# flowerfriend_rev3.net
KiCad netlist of a schematic drawn in EAGLE
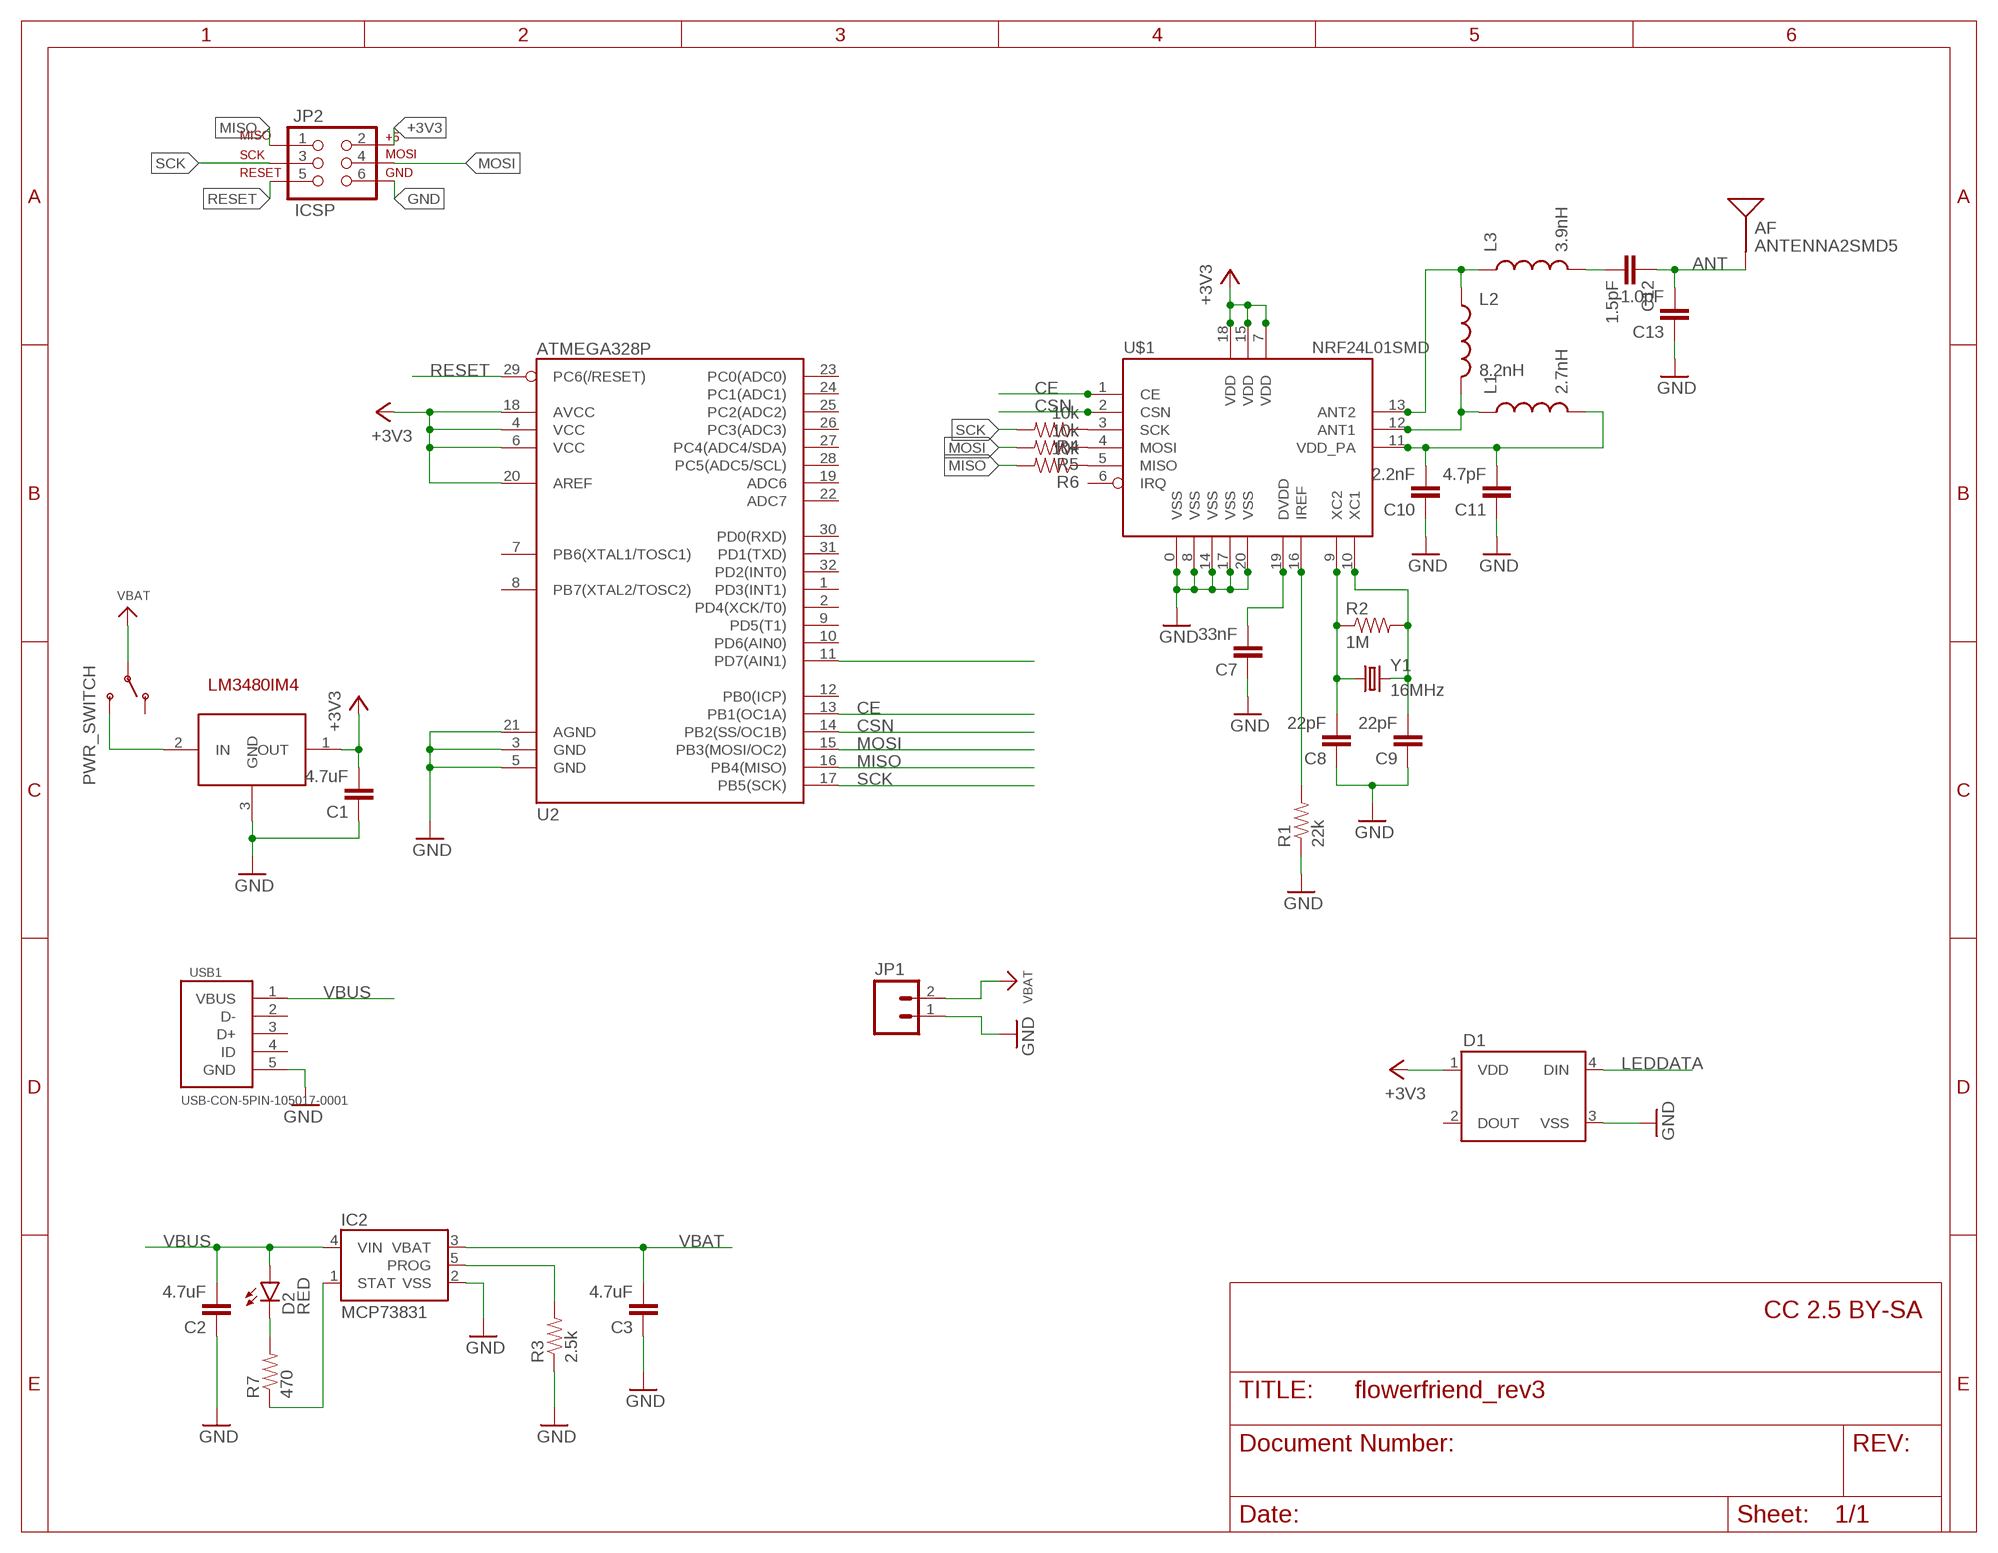
[diagram p0: schematic, sheet 1]

(export (version "E")
  (design (tool "Eeschema 10.0.6"))
  (components
    (comp (ref "AF")
      (value "ANTENNA2SMD5")
      (footprint "eagle-import:ANTENNA-CHIP5")
      (libsource (lib "eagle-import") (part "ANTENNA2SMD5"))
    )
    (comp (ref "C1")
      (value "4.7uF")
      (footprint "eagle-import:0805")
      (libsource (lib "eagle-import") (part "CAP0805"))
    )
    (comp (ref "C2")
      (value "4.7uF")
      (footprint "eagle-import:0805")
      (libsource (lib "eagle-import") (part "CAP0805"))
    )
    (comp (ref "C3")
      (value "4.7uF")
      (footprint "eagle-import:0805")
      (libsource (lib "eagle-import") (part "CAP0805"))
    )
    (comp (ref "C7")
      (value "33nF")
      (footprint "eagle-import:0805")
      (libsource (lib "eagle-import") (part "CAP0805"))
    )
    (comp (ref "C8")
      (value "22pF")
      (footprint "eagle-import:0805")
      (libsource (lib "eagle-import") (part "CAP0805"))
    )
    (comp (ref "C9")
      (value "22pF")
      (footprint "eagle-import:0805")
      (libsource (lib "eagle-import") (part "CAP0805"))
    )
    (comp (ref "C10")
      (value "2.2nF")
      (footprint "eagle-import:0805")
      (libsource (lib "eagle-import") (part "CAP0805"))
    )
    (comp (ref "C11")
      (value "4.7pF")
      (footprint "eagle-import:0805")
      (libsource (lib "eagle-import") (part "CAP0805"))
    )
    (comp (ref "C12")
      (value "1.5pF")
      (footprint "eagle-import:0805")
      (libsource (lib "eagle-import") (part "CAP0805"))
    )
    (comp (ref "C13")
      (value "1.0pF")
      (footprint "eagle-import:0805")
      (libsource (lib "eagle-import") (part "CAP0805"))
    )
    (comp (ref "D1")
      (value "WS2812B")
      (footprint "eagle-import:WS2812B")
      (libsource (lib "eagle-import") (part "WS2812B"))
    )
    (comp (ref "D2")
      (value "RED")
      (footprint "eagle-import:LED-0603")
      (libsource (lib "eagle-import") (part "LED-RED0603"))
    )
    (comp (ref "IC1")
      (value "LM3480IM4")
      (footprint "eagle-import:SOT23-3")
      (libsource (lib "eagle-import") (part "LM3480IM4"))
    )
    (comp (ref "IC2")
      (value "MCP73831")
      (footprint "eagle-import:SOT23-5")
      (libsource (lib "eagle-import") (part "MCP73831"))
    )
    (comp (ref "JP1")
      (value "M02PTH")
      (footprint "eagle-import:1X02")
      (libsource (lib "eagle-import") (part "M02PTH"))
    )
    (comp (ref "JP2")
      (value "ICSP")
      (footprint "eagle-import:2X3")
      (libsource (lib "eagle-import") (part "AVR_SPI_PRG_6PTH"))
    )
    (comp (ref "L1")
      (value "2.7nH")
      (footprint "eagle-import:0805")
      (libsource (lib "eagle-import") (part "INDUCTOR0805"))
    )
    (comp (ref "L2")
      (value "8.2nH")
      (footprint "eagle-import:0805")
      (libsource (lib "eagle-import") (part "INDUCTOR0805"))
    )
    (comp (ref "L3")
      (value "3.9nH")
      (footprint "eagle-import:0805")
      (libsource (lib "eagle-import") (part "INDUCTOR0805"))
    )
    (comp (ref "PWR_SWITCH")
      (value "SWITCH_SPDT")
      (footprint "eagle-import:KPS-1290")
      (libsource (lib "eagle-import") (part "SWITCH_SPDT"))
    )
    (comp (ref "R1")
      (value "22k")
      (footprint "eagle-import:0805")
      (libsource (lib "eagle-import") (part "RESISTOR0805-RES"))
    )
    (comp (ref "R2")
      (value "1M")
      (footprint "eagle-import:0805")
      (libsource (lib "eagle-import") (part "RESISTOR0805-RES"))
    )
    (comp (ref "R3")
      (value "2.5k")
      (footprint "eagle-import:0805")
      (libsource (lib "eagle-import") (part "RESISTOR0805-RES"))
    )
    (comp (ref "R4")
      (value "10k")
      (footprint "eagle-import:0805")
      (libsource (lib "eagle-import") (part "RESISTOR0805-RES"))
    )
    (comp (ref "R5")
      (value "10k")
      (footprint "eagle-import:0805")
      (libsource (lib "eagle-import") (part "RESISTOR0805-RES"))
    )
    (comp (ref "R6")
      (value "10k")
      (footprint "eagle-import:0805")
      (libsource (lib "eagle-import") (part "RESISTOR0805-RES"))
    )
    (comp (ref "R7")
      (value "470")
      (footprint "eagle-import:0805")
      (libsource (lib "eagle-import") (part "RESISTOR0805-RES"))
    )
    (comp (ref "U$1")
      (value "NRF24L01SMD")
      (footprint "eagle-import:QFN20")
      (libsource (lib "eagle-import") (part "NRF24L01SMD"))
    )
    (comp (ref "U2")
      (value "ATMEGA328P")
      (footprint "eagle-import:TQFP32-08")
      (libsource (lib "eagle-import") (part "ATMEGA328_SMT"))
    )
    (comp (ref "USB1")
      (value "USB-CON-5PIN-105017-0001")
      (footprint "eagle-import:USB-MICRO-MOLEX-105017-0001")
      (libsource (lib "eagle-import") (part "USB-CON-5PIN-105017-0001"))
    )
    (comp (ref "Y1")
      (value "16MHz")
      (footprint "eagle-import:CRYSTAL-SMD-5X3")
      (libsource (lib "eagle-import") (part "CRYSTAL5X3"))
    )
  )
  (nets
    (net (code "1") (name "+3V3") (class "Default")
      (node (ref "C1") (pin "2") (pinfunction "2_2") (pintype "passive"))
      (node (ref "D1") (pin "1") (pinfunction "VDD_1") (pintype "power_in"))
      (node (ref "IC1") (pin "1") (pinfunction "OUT_1") (pintype "bidirectional"))
      (node (ref "JP2") (pin "2") (pinfunction "2_2") (pintype "passive"))
      (node (ref "U$1") (pin "15") (pinfunction "VDD_15") (pintype "power_in"))
      (node (ref "U$1") (pin "18") (pinfunction "VDD_18") (pintype "power_in"))
      (node (ref "U$1") (pin "7") (pinfunction "VDD_7") (pintype "power_in"))
      (node (ref "U2") (pin "18") (pinfunction "AVCC_18") (pintype "bidirectional"))
      (node (ref "U2") (pin "20") (pinfunction "AREF_20") (pintype "bidirectional"))
      (node (ref "U2") (pin "4") (pinfunction "VCC_4") (pintype "bidirectional"))
      (node (ref "U2") (pin "6") (pinfunction "VCC_6") (pintype "bidirectional"))
    )
    (net (code "2") (name "/ANT") (class "Default")
      (node (ref "AF") (pin "FEED") (pinfunction "SIGNAL_FEED") (pintype "bidirectional"))
      (node (ref "C12") (pin "1") (pinfunction "1_1") (pintype "passive"))
      (node (ref "C13") (pin "2") (pinfunction "2_2") (pintype "passive"))
    )
    (net (code "3") (name "/CE") (class "Default")
      (node (ref "U$1") (pin "1") (pinfunction "CE_1") (pintype "input"))
      (node (ref "U2") (pin "13") (pinfunction "PB1(OC1A)_13") (pintype "bidirectional"))
    )
    (net (code "4") (name "/CSN") (class "Default")
      (node (ref "U$1") (pin "2") (pinfunction "CSN_2") (pintype "input"))
      (node (ref "U2") (pin "14") (pinfunction "PB2(SS/OC1B)_14") (pintype "bidirectional"))
    )
    (net (code "5") (name "/LEDDATA") (class "Default")
      (node (ref "D1") (pin "4") (pinfunction "DIN_4") (pintype "input"))
      (node (ref "U2") (pin "11") (pinfunction "PD7(AIN1)_11") (pintype "bidirectional"))
    )
    (net (code "6") (name "/VBUS") (class "Default")
      (node (ref "C2") (pin "2") (pinfunction "2_2") (pintype "passive"))
      (node (ref "D2") (pin "A") (pinfunction "A_A") (pintype "passive"))
      (node (ref "IC2") (pin "4") (pinfunction "VIN_4") (pintype "power_in"))
      (node (ref "USB1") (pin "1") (pinfunction "VBUS_1") (pintype "power_in"))
    )
    (net (code "7") (name "GND") (class "Default")
      (node (ref "C1") (pin "1") (pinfunction "1_1") (pintype "passive"))
      (node (ref "C10") (pin "1") (pinfunction "1_1") (pintype "passive"))
      (node (ref "C11") (pin "1") (pinfunction "1_1") (pintype "passive"))
      (node (ref "C13") (pin "1") (pinfunction "1_1") (pintype "passive"))
      (node (ref "C2") (pin "1") (pinfunction "1_1") (pintype "passive"))
      (node (ref "C3") (pin "1") (pinfunction "1_1") (pintype "passive"))
      (node (ref "C7") (pin "1") (pinfunction "1_1") (pintype "passive"))
      (node (ref "C8") (pin "1") (pinfunction "1_1") (pintype "passive"))
      (node (ref "C9") (pin "1") (pinfunction "1_1") (pintype "passive"))
      (node (ref "D1") (pin "3") (pinfunction "VSS_3") (pintype "power_in"))
      (node (ref "IC1") (pin "3") (pinfunction "GND_3") (pintype "bidirectional"))
      (node (ref "IC2") (pin "2") (pinfunction "VSS_2") (pintype "power_in"))
      (node (ref "JP1") (pin "1") (pinfunction "1_1") (pintype "passive"))
      (node (ref "JP2") (pin "6") (pinfunction "6_6") (pintype "passive"))
      (node (ref "R1") (pin "1") (pinfunction "1_1") (pintype "passive"))
      (node (ref "R3") (pin "1") (pinfunction "1_1") (pintype "passive"))
      (node (ref "U$1") (pin "0") (pinfunction "VSS_0") (pintype "power_in"))
      (node (ref "U$1") (pin "14") (pinfunction "VSS_14") (pintype "power_in"))
      (node (ref "U$1") (pin "17") (pinfunction "VSS_17") (pintype "power_in"))
      (node (ref "U$1") (pin "20") (pinfunction "VSS_20") (pintype "power_in"))
      (node (ref "U$1") (pin "8") (pinfunction "VSS_8") (pintype "power_in"))
      (node (ref "U2") (pin "21") (pinfunction "AGND_21") (pintype "bidirectional"))
      (node (ref "U2") (pin "3") (pinfunction "GND_3") (pintype "bidirectional"))
      (node (ref "U2") (pin "5") (pinfunction "GND_5") (pintype "bidirectional"))
      (node (ref "USB1") (pin "5") (pinfunction "GND_5") (pintype "power_in"))
    )
    (net (code "8") (name "MISO") (class "Default")
      (node (ref "JP2") (pin "1") (pinfunction "1_1") (pintype "passive"))
      (node (ref "R6") (pin "2") (pinfunction "2_2") (pintype "passive"))
      (node (ref "U2") (pin "16") (pinfunction "PB4(MISO)_16") (pintype "bidirectional"))
    )
    (net (code "9") (name "MOSI") (class "Default")
      (node (ref "JP2") (pin "4") (pinfunction "4_4") (pintype "passive"))
      (node (ref "R5") (pin "2") (pinfunction "2_2") (pintype "passive"))
      (node (ref "U2") (pin "15") (pinfunction "PB3(MOSI/OC2)_15") (pintype "bidirectional"))
    )
    (net (code "10") (name "Net-(C12-Pad2)") (class "Default")
      (node (ref "C12") (pin "2") (pinfunction "2_2") (pintype "passive"))
      (node (ref "L3") (pin "2") (pinfunction "2_2") (pintype "passive"))
    )
    (net (code "11") (name "Net-(D2-PadC)") (class "Default")
      (node (ref "D2") (pin "C") (pinfunction "C_C") (pintype "passive"))
      (node (ref "R7") (pin "2") (pinfunction "2_2") (pintype "passive"))
    )
    (net (code "12") (name "Net-(IC1-IN)") (class "Default")
      (node (ref "IC1") (pin "2") (pinfunction "IN_2") (pintype "bidirectional"))
      (node (ref "PWR_SWITCH") (pin "S") (pinfunction "S_S") (pintype "passive"))
    )
    (net (code "13") (name "Net-(IC2-PROG)") (class "Default")
      (node (ref "IC2") (pin "5") (pinfunction "PROG_5") (pintype "input"))
      (node (ref "R3") (pin "2") (pinfunction "2_2") (pintype "passive"))
    )
    (net (code "14") (name "Net-(IC2-STAT)") (class "Default")
      (node (ref "IC2") (pin "1") (pinfunction "STAT_1") (pintype "output"))
      (node (ref "R7") (pin "1") (pinfunction "1_1") (pintype "passive"))
    )
    (net (code "15") (name "Net-(U$1-ANT1)") (class "Default")
      (node (ref "L1") (pin "1") (pinfunction "1_1") (pintype "passive"))
      (node (ref "L2") (pin "2") (pinfunction "2_2") (pintype "passive"))
      (node (ref "U$1") (pin "12") (pinfunction "ANT1_12") (pintype "output"))
    )
    (net (code "16") (name "Net-(U$1-ANT2)") (class "Default")
      (node (ref "L2") (pin "1") (pinfunction "1_1") (pintype "passive"))
      (node (ref "L3") (pin "1") (pinfunction "1_1") (pintype "passive"))
      (node (ref "U$1") (pin "13") (pinfunction "ANT2_13") (pintype "output"))
    )
    (net (code "17") (name "Net-(U$1-DVDD)") (class "Default")
      (node (ref "C7") (pin "2") (pinfunction "2_2") (pintype "passive"))
      (node (ref "U$1") (pin "19") (pinfunction "DVDD_19") (pintype "power_in"))
    )
    (net (code "18") (name "Net-(U$1-IREF)") (class "Default")
      (node (ref "R1") (pin "2") (pinfunction "2_2") (pintype "passive"))
      (node (ref "U$1") (pin "16") (pinfunction "IREF_16") (pintype "input"))
    )
    (net (code "19") (name "Net-(U$1-MISO)") (class "Default")
      (node (ref "R6") (pin "1") (pinfunction "1_1") (pintype "passive"))
      (node (ref "U$1") (pin "5") (pinfunction "MISO_5") (pintype "output"))
    )
    (net (code "20") (name "Net-(U$1-MOSI)") (class "Default")
      (node (ref "R5") (pin "1") (pinfunction "1_1") (pintype "passive"))
      (node (ref "U$1") (pin "4") (pinfunction "MOSI_4") (pintype "input"))
    )
    (net (code "21") (name "Net-(U$1-SCK)") (class "Default")
      (node (ref "R4") (pin "1") (pinfunction "1_1") (pintype "passive"))
      (node (ref "U$1") (pin "3") (pinfunction "SCK_3") (pintype "input"))
    )
    (net (code "22") (name "Net-(U$1-VDD_PA)") (class "Default")
      (node (ref "C10") (pin "2") (pinfunction "2_2") (pintype "passive"))
      (node (ref "C11") (pin "2") (pinfunction "2_2") (pintype "passive"))
      (node (ref "L1") (pin "2") (pinfunction "2_2") (pintype "passive"))
      (node (ref "U$1") (pin "11") (pinfunction "VDD_PA_11") (pintype "power_in"))
    )
    (net (code "23") (name "Net-(U$1-XC1)") (class "Default")
      (node (ref "C9") (pin "2") (pinfunction "2_2") (pintype "passive"))
      (node (ref "R2") (pin "2") (pinfunction "2_2") (pintype "passive"))
      (node (ref "U$1") (pin "10") (pinfunction "XC1_10") (pintype "input"))
      (node (ref "Y1") (pin "3") (pinfunction "2_3") (pintype "passive"))
    )
    (net (code "24") (name "Net-(U$1-XC2)") (class "Default")
      (node (ref "C8") (pin "2") (pinfunction "2_2") (pintype "passive"))
      (node (ref "R2") (pin "1") (pinfunction "1_1") (pintype "passive"))
      (node (ref "U$1") (pin "9") (pinfunction "XC2_9") (pintype "input"))
      (node (ref "Y1") (pin "1") (pinfunction "1_1") (pintype "passive"))
    )
    (net (code "25") (name "RESET") (class "Default")
      (node (ref "JP2") (pin "5") (pinfunction "5_5") (pintype "passive"))
      (node (ref "U2") (pin "29") (pinfunction "PC6(/RESET)_29") (pintype "bidirectional"))
    )
    (net (code "26") (name "SCK") (class "Default")
      (node (ref "JP2") (pin "3") (pinfunction "3_3") (pintype "passive"))
      (node (ref "R4") (pin "2") (pinfunction "2_2") (pintype "passive"))
      (node (ref "U2") (pin "17") (pinfunction "PB5(SCK)_17") (pintype "bidirectional"))
    )
    (net (code "27") (name "VBAT") (class "Default")
      (node (ref "C3") (pin "2") (pinfunction "2_2") (pintype "passive"))
      (node (ref "IC2") (pin "3") (pinfunction "VBAT_3") (pintype "power_in"))
      (node (ref "JP1") (pin "2") (pinfunction "2_2") (pintype "passive"))
      (node (ref "PWR_SWITCH") (pin "P") (pinfunction "P_P") (pintype "passive"))
    )
    (net (code "28") (name "unconnected-(D1-DOUT-Pad2)") (class "Default")
      (node (ref "D1") (pin "2") (pinfunction "DOUT_2") (pintype "output"))
    )
    (net (code "29") (name "unconnected-(PWR_SWITCH-PadO)") (class "Default")
      (node (ref "PWR_SWITCH") (pin "O") (pinfunction "O_O") (pintype "passive"))
    )
    (net (code "30") (name "unconnected-(U$1-IRQ-Pad6)") (class "Default")
      (node (ref "U$1") (pin "6") (pinfunction "IRQ_6") (pintype "output"))
    )
    (net (code "31") (name "unconnected-(U2-ADC6-Pad19)") (class "Default")
      (node (ref "U2") (pin "19") (pinfunction "ADC6_19") (pintype "bidirectional"))
    )
    (net (code "32") (name "unconnected-(U2-ADC7-Pad22)") (class "Default")
      (node (ref "U2") (pin "22") (pinfunction "ADC7_22") (pintype "bidirectional"))
    )
    (net (code "33") (name "unconnected-(U2-PB0(ICP)-Pad12)") (class "Default")
      (node (ref "U2") (pin "12") (pinfunction "PB0(ICP)_12") (pintype "bidirectional"))
    )
    (net (code "34") (name "unconnected-(U2-PB6(XTAL1{slash}TOSC1)-Pad7)") (class "Default")
      (node (ref "U2") (pin "7") (pinfunction "PB6(XTAL1/TOSC1)_7") (pintype "bidirectional"))
    )
    (net (code "35") (name "unconnected-(U2-PB7(XTAL2{slash}TOSC2)-Pad8)") (class "Default")
      (node (ref "U2") (pin "8") (pinfunction "PB7(XTAL2/TOSC2)_8") (pintype "bidirectional"))
    )
    (net (code "36") (name "unconnected-(U2-PC0(ADC0)-Pad23)") (class "Default")
      (node (ref "U2") (pin "23") (pinfunction "PC0(ADC0)_23") (pintype "bidirectional"))
    )
    (net (code "37") (name "unconnected-(U2-PC1(ADC1)-Pad24)") (class "Default")
      (node (ref "U2") (pin "24") (pinfunction "PC1(ADC1)_24") (pintype "bidirectional"))
    )
    (net (code "38") (name "unconnected-(U2-PC2(ADC2)-Pad25)") (class "Default")
      (node (ref "U2") (pin "25") (pinfunction "PC2(ADC2)_25") (pintype "bidirectional"))
    )
    (net (code "39") (name "unconnected-(U2-PC3(ADC3)-Pad26)") (class "Default")
      (node (ref "U2") (pin "26") (pinfunction "PC3(ADC3)_26") (pintype "bidirectional"))
    )
    (net (code "40") (name "unconnected-(U2-PC4(ADC4{slash}SDA)-Pad27)") (class "Default")
      (node (ref "U2") (pin "27") (pinfunction "PC4(ADC4/SDA)_27") (pintype "bidirectional"))
    )
    (net (code "41") (name "unconnected-(U2-PC5(ADC5{slash}SCL)-Pad28)") (class "Default")
      (node (ref "U2") (pin "28") (pinfunction "PC5(ADC5/SCL)_28") (pintype "bidirectional"))
    )
    (net (code "42") (name "unconnected-(U2-PD0(RXD)-Pad30)") (class "Default")
      (node (ref "U2") (pin "30") (pinfunction "PD0(RXD)_30") (pintype "bidirectional"))
    )
    (net (code "43") (name "unconnected-(U2-PD1(TXD)-Pad31)") (class "Default")
      (node (ref "U2") (pin "31") (pinfunction "PD1(TXD)_31") (pintype "bidirectional"))
    )
    (net (code "44") (name "unconnected-(U2-PD2(INT0)-Pad32)") (class "Default")
      (node (ref "U2") (pin "32") (pinfunction "PD2(INT0)_32") (pintype "bidirectional"))
    )
    (net (code "45") (name "unconnected-(U2-PD3(INT1)-Pad1)") (class "Default")
      (node (ref "U2") (pin "1") (pinfunction "PD3(INT1)_1") (pintype "bidirectional"))
    )
    (net (code "46") (name "unconnected-(U2-PD4(XCK{slash}T0)-Pad2)") (class "Default")
      (node (ref "U2") (pin "2") (pinfunction "PD4(XCK/T0)_2") (pintype "bidirectional"))
    )
    (net (code "47") (name "unconnected-(U2-PD5(T1)-Pad9)") (class "Default")
      (node (ref "U2") (pin "9") (pinfunction "PD5(T1)_9") (pintype "bidirectional"))
    )
    (net (code "48") (name "unconnected-(U2-PD6(AIN0)-Pad10)") (class "Default")
      (node (ref "U2") (pin "10") (pinfunction "PD6(AIN0)_10") (pintype "bidirectional"))
    )
    (net (code "49") (name "unconnected-(USB1-D+-Pad3)") (class "Default")
      (node (ref "USB1") (pin "3") (pinfunction "D+_3") (pintype "bidirectional"))
    )
    (net (code "50") (name "unconnected-(USB1-D--Pad2)") (class "Default")
      (node (ref "USB1") (pin "2") (pinfunction "D-_2") (pintype "bidirectional"))
    )
    (net (code "51") (name "unconnected-(USB1-ID-Pad4)") (class "Default")
      (node (ref "USB1") (pin "4") (pinfunction "ID_4") (pintype "bidirectional"))
    )
  )
)
